# NodeSpeed.net
KiCad netlist of a schematic drawn in Altium Designer
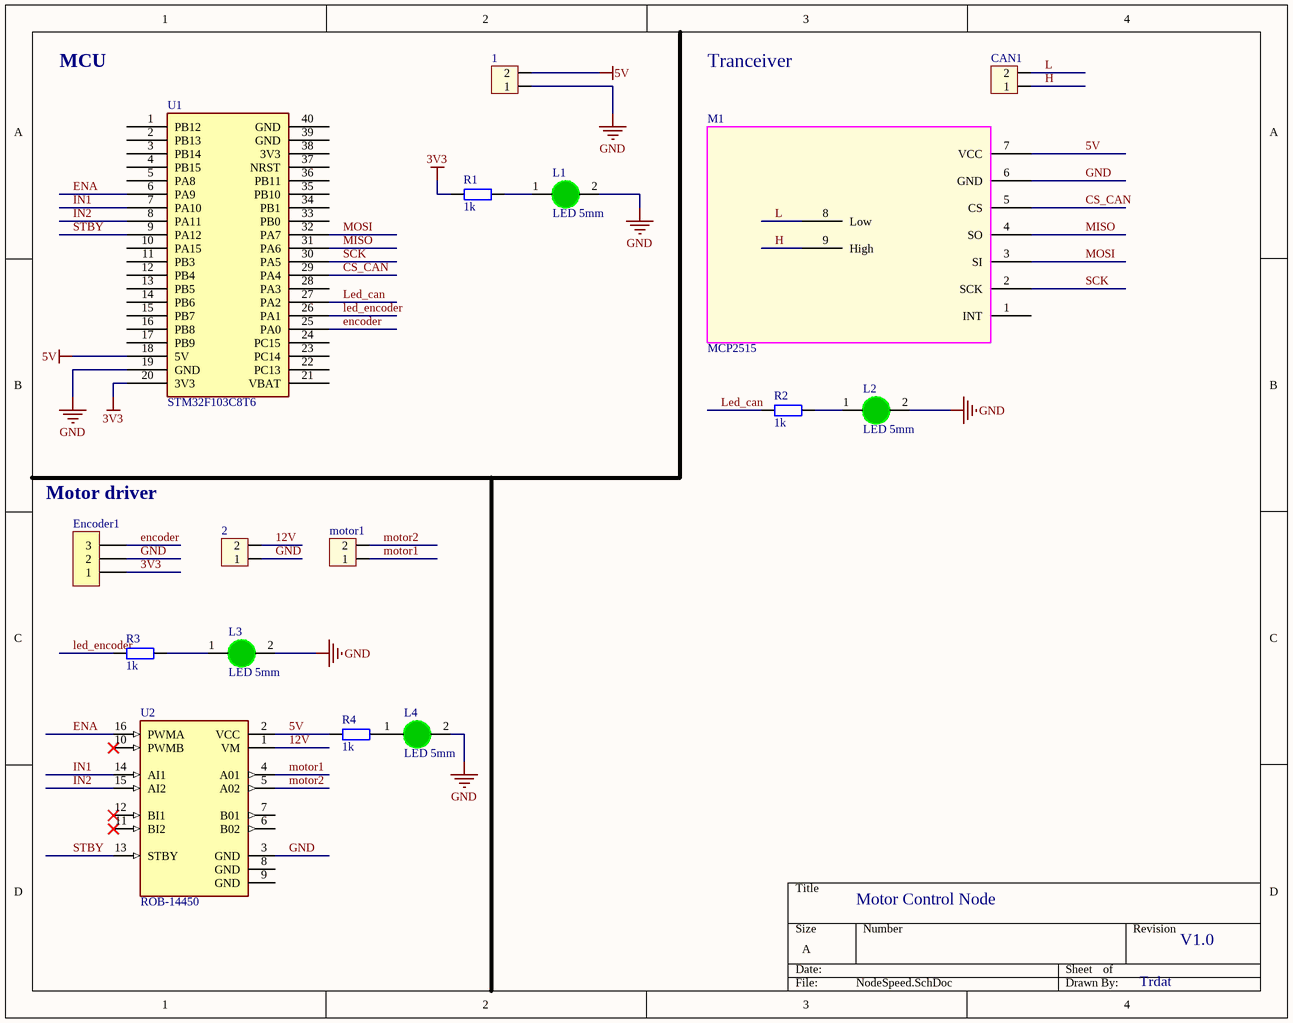
[diagram p0: NodeSpeed.SchDoc]

(export (version "E")
  (design (tool "Eeschema 10.0.6"))
  (components
    (comp (ref "1")
      (value "Header 2P 2.54 Duc Cong")
      (footprint "Header 2P DC 2.54")
      (description "Cắm")
      (libsource (lib "Altium_Lib_by_KhueNguyenCreator") (part "Header 2P 2.54 Duc Cong"))
    )
    (comp (ref "2")
      (value "Header 2P 2.54 Duc Cong")
      (footprint "Header 2P DC 2.54")
      (description "Cắm")
      (libsource (lib "Altium_Lib_by_KhueNguyenCreator") (part "Header 2P 2.54 Duc Cong"))
    )
    (comp (ref "CAN1")
      (value "~")
      (footprint "Header 2P DC 2.54")
      (description "Cắm")
      (libsource (lib "Altium_Lib_by_KhueNguyenCreator") (part "Header 2P 2.54 Duc Cong"))
    )
    (comp (ref "Encoder1")
      (value "Header 3P 2.54 Duc Cong")
      (footprint "Header 3P DC 2.54")
      (description "Cắm")
      (libsource (lib "Altium_Lib_by_KhueNguyenCreator") (part "Header 3P 2.54 Duc Cong"))
    )
    (comp (ref "L1")
      (value "LED 5mm")
      (footprint "LED-5MM-Green")
      (description "Cắm")
      (libsource (lib "Altium_Lib_by_KhueNguyenCreator") (part "LED 5mm Xanh La"))
    )
    (comp (ref "L2")
      (value "LED 5mm")
      (footprint "LED-5MM-Green")
      (description "Cắm")
      (libsource (lib "Altium_Lib_by_KhueNguyenCreator") (part "LED 5mm Xanh La"))
    )
    (comp (ref "L3")
      (value "LED 5mm")
      (footprint "LED-5MM-Green")
      (description "Cắm")
      (libsource (lib "Altium_Lib_by_KhueNguyenCreator") (part "LED 5mm Xanh La"))
    )
    (comp (ref "L4")
      (value "LED 5mm")
      (footprint "LED-5MM-Green")
      (description "Cắm")
      (libsource (lib "Altium_Lib_by_KhueNguyenCreator") (part "LED 5mm Xanh La"))
    )
    (comp (ref "M1")
      (value "MCP2515")
      (footprint "MCP2515_MODULE")
      (libsource (lib "My_Component_Library") (part "MCP2515"))
    )
    (comp (ref "motor1")
      (value "~")
      (footprint "Header 2P DC 2.54")
      (description "Cắm")
      (libsource (lib "Altium_Lib_by_KhueNguyenCreator") (part "Header 2P 2.54 Duc Cong"))
    )
    (comp (ref "R1")
      (value "1k")
      (footprint "tro vach 1/4w")
      (description "Cắm")
      (libsource (lib "Altium_Lib_by_KhueNguyenCreator") (part "Tro Vach 1/4W 5% 1k"))
    )
    (comp (ref "R2")
      (value "1k")
      (footprint "tro vach 1/4w")
      (description "Cắm")
      (libsource (lib "Altium_Lib_by_KhueNguyenCreator") (part "Tro Vach 1/4W 5% 1k"))
    )
    (comp (ref "R3")
      (value "1k")
      (footprint "tro vach 1/4w")
      (description "Cắm")
      (libsource (lib "Altium_Lib_by_KhueNguyenCreator") (part "Tro Vach 1/4W 5% 1k"))
    )
    (comp (ref "R4")
      (value "1k")
      (footprint "tro vach 1/4w")
      (description "Cắm")
      (libsource (lib "Altium_Lib_by_KhueNguyenCreator") (part "Tro Vach 1/4W 5% 1k"))
    )
    (comp (ref "U1")
      (value "STM32F103C8T6")
      (footprint "Stm32 BluePill")
      (description "Designed By @Alixahedi")
      (libsource (lib "Stm32 Blue Pill") (part "BluePill"))
    )
    (comp (ref "U2")
      (value "ROB-14450")
      (footprint "MODULE_ROB-14450")
      (description "TB6612FNG Motor Controller/Driver Power Management Evaluation Board")
      (fields (field (name "MF") "SparkFun Electronics"))
      (libsource (lib "ROB-14450") (part "ROB-14450"))
    )
  )
  (nets
    (net (code "1") (name "/12V") (class "Default")
      (node (ref "2") (pin "2") (pinfunction "2_2") (pintype "passive"))
      (node (ref "U2") (pin "1") (pinfunction "VM_1") (pintype "power_in"))
    )
    (net (code "2") (name "/CS_CAN") (class "Default")
      (node (ref "M1") (pin "5") (pinfunction "CS_5") (pintype "passive"))
      (node (ref "U1") (pin "29") (pinfunction "PA4_29") (pintype "passive"))
    )
    (net (code "3") (name "/ENA") (class "Default")
      (node (ref "U1") (pin "6") (pinfunction "PA9_6") (pintype "passive"))
      (node (ref "U2") (pin "16") (pinfunction "PWMA_16") (pintype "input"))
    )
    (net (code "4") (name "/H") (class "Default")
      (node (ref "CAN1") (pin "1") (pinfunction "1_1") (pintype "passive"))
      (node (ref "M1") (pin "9") (pinfunction "High_9") (pintype "passive"))
    )
    (net (code "5") (name "/IN1") (class "Default")
      (node (ref "U1") (pin "7") (pinfunction "PA10_7") (pintype "passive"))
      (node (ref "U2") (pin "14") (pinfunction "AI1_14") (pintype "input"))
    )
    (net (code "6") (name "/IN2") (class "Default")
      (node (ref "U1") (pin "8") (pinfunction "PA11_8") (pintype "passive"))
      (node (ref "U2") (pin "15") (pinfunction "AI2_15") (pintype "input"))
    )
    (net (code "7") (name "/L") (class "Default")
      (node (ref "CAN1") (pin "2") (pinfunction "2_2") (pintype "passive"))
      (node (ref "M1") (pin "8") (pinfunction "Low_8") (pintype "passive"))
    )
    (net (code "8") (name "/Led_can") (class "Default")
      (node (ref "R2") (pin "1") (pinfunction "1_1") (pintype "passive"))
      (node (ref "U1") (pin "27") (pinfunction "PA2_27") (pintype "passive"))
    )
    (net (code "9") (name "/MISO") (class "Default")
      (node (ref "M1") (pin "4") (pinfunction "SO_4") (pintype "passive"))
      (node (ref "U1") (pin "31") (pinfunction "PA6_31") (pintype "passive"))
    )
    (net (code "10") (name "/MOSI") (class "Default")
      (node (ref "M1") (pin "3") (pinfunction "SI_3") (pintype "passive"))
      (node (ref "U1") (pin "32") (pinfunction "PA7_32") (pintype "passive"))
    )
    (net (code "11") (name "/SCK") (class "Default")
      (node (ref "M1") (pin "2") (pinfunction "SCK_2") (pintype "passive"))
      (node (ref "U1") (pin "30") (pinfunction "PA5_30") (pintype "passive"))
    )
    (net (code "12") (name "/STBY") (class "Default")
      (node (ref "U1") (pin "9") (pinfunction "PA12_9") (pintype "passive"))
      (node (ref "U2") (pin "13") (pinfunction "STBY_13") (pintype "input"))
    )
    (net (code "13") (name "/encoder") (class "Default")
      (node (ref "Encoder1") (pin "3") (pinfunction "3_3") (pintype "passive"))
      (node (ref "U1") (pin "25") (pinfunction "PA0_25") (pintype "passive"))
    )
    (net (code "14") (name "/led_encoder") (class "Default")
      (node (ref "R3") (pin "1") (pinfunction "1_1") (pintype "passive"))
      (node (ref "U1") (pin "26") (pinfunction "PA1_26") (pintype "passive"))
    )
    (net (code "15") (name "/motor1") (class "Default")
      (node (ref "U2") (pin "4") (pinfunction "A01_4") (pintype "output"))
      (node (ref "motor1") (pin "1") (pinfunction "1_1") (pintype "passive"))
    )
    (net (code "16") (name "/motor2") (class "Default")
      (node (ref "U2") (pin "5") (pinfunction "A02_5") (pintype "output"))
      (node (ref "motor1") (pin "2") (pinfunction "2_2") (pintype "passive"))
    )
    (net (code "17") (name "3V3") (class "Default")
      (node (ref "Encoder1") (pin "1") (pinfunction "1_1") (pintype "passive"))
      (node (ref "R1") (pin "1") (pinfunction "1_1") (pintype "passive"))
      (node (ref "U1") (pin "20") (pinfunction "3V3_20") (pintype "passive"))
    )
    (net (code "18") (name "5V") (class "Default")
      (node (ref "1") (pin "2") (pinfunction "2_2") (pintype "passive"))
      (node (ref "M1") (pin "7") (pinfunction "VCC_7") (pintype "power_in"))
      (node (ref "R4") (pin "1") (pinfunction "1_1") (pintype "passive"))
      (node (ref "U1") (pin "18") (pinfunction "5V_18") (pintype "passive"))
      (node (ref "U2") (pin "2") (pinfunction "VCC_2") (pintype "power_in"))
    )
    (net (code "19") (name "GND") (class "Default")
      (node (ref "1") (pin "1") (pinfunction "1_1") (pintype "passive"))
      (node (ref "2") (pin "1") (pinfunction "1_1") (pintype "passive"))
      (node (ref "Encoder1") (pin "2") (pinfunction "2_2") (pintype "passive"))
      (node (ref "L1") (pin "2") (pinfunction "K_2") (pintype "passive"))
      (node (ref "L2") (pin "2") (pinfunction "K_2") (pintype "passive"))
      (node (ref "L3") (pin "2") (pinfunction "K_2") (pintype "passive"))
      (node (ref "L4") (pin "2") (pinfunction "K_2") (pintype "passive"))
      (node (ref "M1") (pin "6") (pinfunction "GND_6") (pintype "power_in"))
      (node (ref "U1") (pin "19") (pinfunction "GND_19") (pintype "passive"))
      (node (ref "U2") (pin "3") (pinfunction "GND_3") (pintype "power_in"))
    )
    (net (code "20") (name "Net-(L1-A)") (class "Default")
      (node (ref "L1") (pin "1") (pinfunction "A_1") (pintype "passive"))
      (node (ref "R1") (pin "2") (pinfunction "2_2") (pintype "passive"))
    )
    (net (code "21") (name "Net-(L2-A)") (class "Default")
      (node (ref "L2") (pin "1") (pinfunction "A_1") (pintype "passive"))
      (node (ref "R2") (pin "2") (pinfunction "2_2") (pintype "passive"))
    )
    (net (code "22") (name "Net-(L3-A)") (class "Default")
      (node (ref "L3") (pin "1") (pinfunction "A_1") (pintype "passive"))
      (node (ref "R3") (pin "2") (pinfunction "2_2") (pintype "passive"))
    )
    (net (code "23") (name "Net-(L4-A)") (class "Default")
      (node (ref "L4") (pin "1") (pinfunction "A_1") (pintype "passive"))
      (node (ref "R4") (pin "2") (pinfunction "2_2") (pintype "passive"))
    )
    (net (code "24") (name "unconnected-(M1-INT-Pad1)") (class "Default")
      (node (ref "M1") (pin "1") (pinfunction "INT_1") (pintype "passive"))
    )
    (net (code "25") (name "unconnected-(U1-3V3-Pad38)") (class "Default")
      (node (ref "U1") (pin "38") (pinfunction "3V3_38") (pintype "passive"))
    )
    (net (code "26") (name "unconnected-(U1-GND-Pad39)") (class "Default")
      (node (ref "U1") (pin "39") (pinfunction "GND_39") (pintype "passive"))
    )
    (net (code "27") (name "unconnected-(U1-GND-Pad40)") (class "Default")
      (node (ref "U1") (pin "40") (pinfunction "GND_40") (pintype "passive"))
    )
    (net (code "28") (name "unconnected-(U1-NRST-Pad37)") (class "Default")
      (node (ref "U1") (pin "37") (pinfunction "NRST_37") (pintype "passive"))
    )
    (net (code "29") (name "unconnected-(U1-PA3-Pad28)") (class "Default")
      (node (ref "U1") (pin "28") (pinfunction "PA3_28") (pintype "passive"))
    )
    (net (code "30") (name "unconnected-(U1-PA8-Pad5)") (class "Default")
      (node (ref "U1") (pin "5") (pinfunction "PA8_5") (pintype "passive"))
    )
    (net (code "31") (name "unconnected-(U1-PA15-Pad10)") (class "Default")
      (node (ref "U1") (pin "10") (pinfunction "PA15_10") (pintype "passive"))
    )
    (net (code "32") (name "unconnected-(U1-PB0-Pad33)") (class "Default")
      (node (ref "U1") (pin "33") (pinfunction "PB0_33") (pintype "passive"))
    )
    (net (code "33") (name "unconnected-(U1-PB1-Pad34)") (class "Default")
      (node (ref "U1") (pin "34") (pinfunction "PB1_34") (pintype "passive"))
    )
    (net (code "34") (name "unconnected-(U1-PB3-Pad11)") (class "Default")
      (node (ref "U1") (pin "11") (pinfunction "PB3_11") (pintype "passive"))
    )
    (net (code "35") (name "unconnected-(U1-PB4-Pad12)") (class "Default")
      (node (ref "U1") (pin "12") (pinfunction "PB4_12") (pintype "passive"))
    )
    (net (code "36") (name "unconnected-(U1-PB5-Pad13)") (class "Default")
      (node (ref "U1") (pin "13") (pinfunction "PB5_13") (pintype "passive"))
    )
    (net (code "37") (name "unconnected-(U1-PB6-Pad14)") (class "Default")
      (node (ref "U1") (pin "14") (pinfunction "PB6_14") (pintype "passive"))
    )
    (net (code "38") (name "unconnected-(U1-PB7-Pad15)") (class "Default")
      (node (ref "U1") (pin "15") (pinfunction "PB7_15") (pintype "passive"))
    )
    (net (code "39") (name "unconnected-(U1-PB8-Pad16)") (class "Default")
      (node (ref "U1") (pin "16") (pinfunction "PB8_16") (pintype "passive"))
    )
    (net (code "40") (name "unconnected-(U1-PB9-Pad17)") (class "Default")
      (node (ref "U1") (pin "17") (pinfunction "PB9_17") (pintype "passive"))
    )
    (net (code "41") (name "unconnected-(U1-PB10-Pad35)") (class "Default")
      (node (ref "U1") (pin "35") (pinfunction "PB10_35") (pintype "passive"))
    )
    (net (code "42") (name "unconnected-(U1-PB11-Pad36)") (class "Default")
      (node (ref "U1") (pin "36") (pinfunction "PB11_36") (pintype "passive"))
    )
    (net (code "43") (name "unconnected-(U1-PB12-Pad1)") (class "Default")
      (node (ref "U1") (pin "1") (pinfunction "PB12_1") (pintype "passive"))
    )
    (net (code "44") (name "unconnected-(U1-PB13-Pad2)") (class "Default")
      (node (ref "U1") (pin "2") (pinfunction "PB13_2") (pintype "passive"))
    )
    (net (code "45") (name "unconnected-(U1-PB14-Pad3)") (class "Default")
      (node (ref "U1") (pin "3") (pinfunction "PB14_3") (pintype "passive"))
    )
    (net (code "46") (name "unconnected-(U1-PB15-Pad4)") (class "Default")
      (node (ref "U1") (pin "4") (pinfunction "PB15_4") (pintype "passive"))
    )
    (net (code "47") (name "unconnected-(U1-PC13-Pad22)") (class "Default")
      (node (ref "U1") (pin "22") (pinfunction "PC13_22") (pintype "passive"))
    )
    (net (code "48") (name "unconnected-(U1-PC14-Pad23)") (class "Default")
      (node (ref "U1") (pin "23") (pinfunction "PC14_23") (pintype "passive"))
    )
    (net (code "49") (name "unconnected-(U1-PC15-Pad24)") (class "Default")
      (node (ref "U1") (pin "24") (pinfunction "PC15_24") (pintype "passive"))
    )
    (net (code "50") (name "unconnected-(U1-VBAT-Pad21)") (class "Default")
      (node (ref "U1") (pin "21") (pinfunction "VBAT_21") (pintype "passive"))
    )
    (net (code "51") (name "unconnected-(U2-B01-Pad7)") (class "Default")
      (node (ref "U2") (pin "7") (pinfunction "B01_7") (pintype "output"))
    )
    (net (code "52") (name "unconnected-(U2-B02-Pad6)") (class "Default")
      (node (ref "U2") (pin "6") (pinfunction "B02_6") (pintype "output"))
    )
    (net (code "53") (name "unconnected-(U2-BI1-Pad12)") (class "Default")
      (node (ref "U2") (pin "12") (pinfunction "BI1_12") (pintype "input+no_connect"))
    )
    (net (code "54") (name "unconnected-(U2-BI2-Pad11)") (class "Default")
      (node (ref "U2") (pin "11") (pinfunction "BI2_11") (pintype "input+no_connect"))
    )
    (net (code "55") (name "unconnected-(U2-GND-Pad8)") (class "Default")
      (node (ref "U2") (pin "8") (pinfunction "GND_8") (pintype "power_in"))
    )
    (net (code "56") (name "unconnected-(U2-GND-Pad9)") (class "Default")
      (node (ref "U2") (pin "9") (pinfunction "GND_9") (pintype "power_in"))
    )
    (net (code "57") (name "unconnected-(U2-PWMB-Pad10)") (class "Default")
      (node (ref "U2") (pin "10") (pinfunction "PWMB_10") (pintype "input+no_connect"))
    )
  )
)
